# 2022_AESK_UAV_CAN.net
KiCad netlist of a schematic drawn in Altium Designer
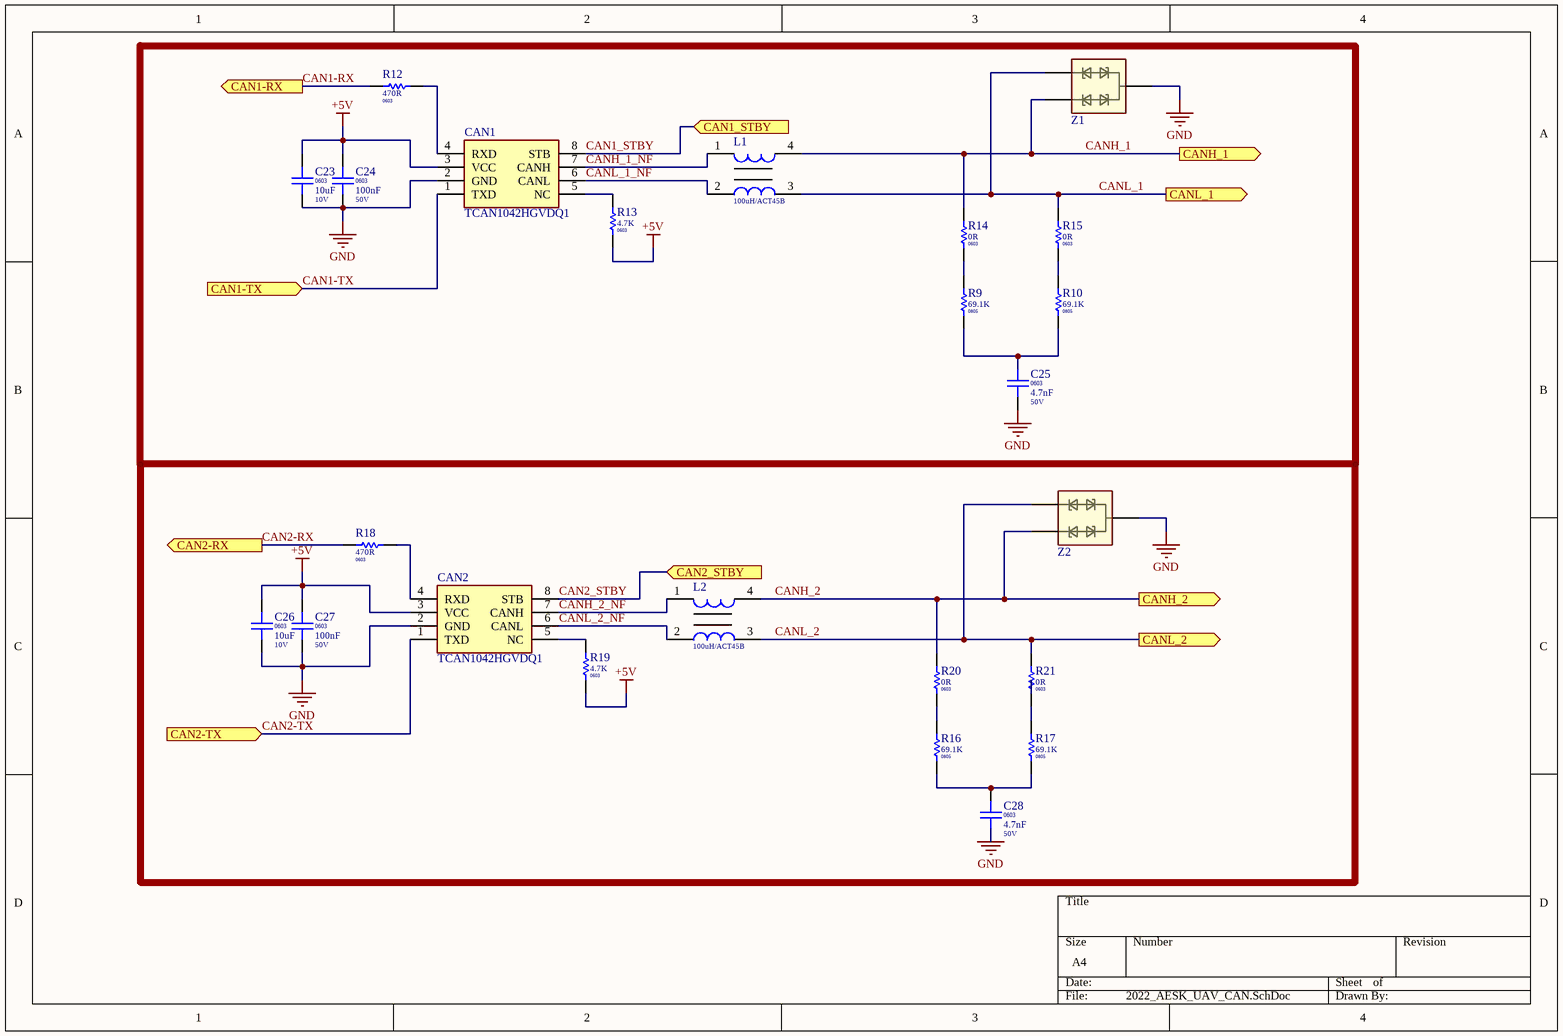
[diagram p0: 2022_AESK_UAV_CAN.SchDoc]

(export (version "E")
  (design (tool "Eeschema 10.0.6"))
  (components
    (comp (ref "C23")
      (value "10uF")
      (footprint "CAPC 0603")
      (description "Capacitor Ceramic 10uF 10V 0603")
      (fields
        (field (name "TOLERANCE") "%10")
        (field (name "PACKAGE / CASE") "0603")
        (field (name "VOLTAGE") "10V")
        (field (name "PART NUMBER") "CAPC0473")
      )
      (libsource (lib "Aesk Database Library") (part "NPCapacitor"))
    )
    (comp (ref "C24")
      (value "100nF")
      (footprint "CAPC 0603")
      (description "Capacitor Ceramic 100nF 50V 0603")
      (fields
        (field (name "TOLERANCE") "%10")
        (field (name "PACKAGE / CASE") "0603")
        (field (name "VOLTAGE") "50V")
        (field (name "PART NUMBER") "CAPC0285")
      )
      (libsource (lib "Aesk Database Library") (part "NPCapacitor"))
    )
    (comp (ref "C25")
      (value "4.7nF")
      (footprint "CAPC 0603")
      (description "Capacitor Ceramic 4.7nF 50V 0603")
      (fields
        (field (name "TOLERANCE") "%10")
        (field (name "PACKAGE / CASE") "0603")
        (field (name "VOLTAGE") "50V")
        (field (name "PART NUMBER") "CAPC0273")
      )
      (libsource (lib "Aesk Database Library") (part "NPCapacitor"))
    )
    (comp (ref "C26")
      (value "10uF")
      (footprint "CAPC 0603")
      (description "Capacitor Ceramic 10uF 10V 0603")
      (fields
        (field (name "TOLERANCE") "%10")
        (field (name "PACKAGE / CASE") "0603")
        (field (name "VOLTAGE") "10V")
        (field (name "PART NUMBER") "CAPC0473")
      )
      (libsource (lib "Aesk Database Library") (part "NPCapacitor"))
    )
    (comp (ref "C27")
      (value "100nF")
      (footprint "CAPC 0603")
      (description "Capacitor Ceramic 100nF 50V 0603")
      (fields
        (field (name "TOLERANCE") "%10")
        (field (name "PACKAGE / CASE") "0603")
        (field (name "VOLTAGE") "50V")
        (field (name "PART NUMBER") "CAPC0285")
      )
      (libsource (lib "Aesk Database Library") (part "NPCapacitor"))
    )
    (comp (ref "C28")
      (value "4.7nF")
      (footprint "CAPC 0603")
      (description "Capacitor Ceramic 4.7nF 50V 0603")
      (fields
        (field (name "TOLERANCE") "%10")
        (field (name "PACKAGE / CASE") "0603")
        (field (name "VOLTAGE") "50V")
        (field (name "PART NUMBER") "CAPC0273")
      )
      (libsource (lib "Aesk Database Library") (part "NPCapacitor"))
    )
    (comp (ref "CAN1")
      (value "TCAN1042HGVDQ1")
      (footprint "SOIC127P600X175-8N")
      (description "Integrated Circuit")
      (fields
        (field (name "MANUFACTURER_PART_NUMBER") "TCAN1042HDRQ1")
        (field (name "MOUSER PART NUMBER") "595-TCAN1042HGVDQ1")
      )
      (libsource (lib "Mainboard_2020_Library") (part "TCAN1042HGVDQ1"))
    )
    (comp (ref "CAN2")
      (value "TCAN1042HGVDQ1")
      (footprint "SOIC127P600X175-8N")
      (description "Integrated Circuit")
      (fields
        (field (name "MANUFACTURER_PART_NUMBER") "TCAN1042HDRQ1")
        (field (name "MOUSER PART NUMBER") "595-TCAN1042HGVDQ1")
      )
      (libsource (lib "Mainboard_2020_Library") (part "TCAN1042HGVDQ1"))
    )
    (comp (ref "L1")
      (value "ACT45B-101-2P-TL003")
      (footprint "TDK_ACT45B_2")
      (description "Inductor")
      (fields (field (name "NAME") "100uH/ACT45B"))
      (libsource (lib "Mainboard_2020_Library") (part "ACT45B-101-2P-TL003"))
    )
    (comp (ref "L2")
      (value "ACT45B-101-2P-TL003")
      (footprint "TDK_ACT45B_2")
      (description "Inductor")
      (fields (field (name "NAME") "100uH/ACT45B"))
      (libsource (lib "Mainboard_2020_Library") (part "ACT45B-101-2P-TL003"))
    )
    (comp (ref "R9")
      (value "69.1K")
      (footprint "RESC 0805")
      (description "68K 0805")
      (fields
        (field (name "TOLERANCE") "%5")
        (field (name "POWER") "1/10W")
        (field (name "PACKAGE / CASE") "0805")
      )
      (libsource (lib "AESK Database Library") (part "Resistor"))
    )
    (comp (ref "R10")
      (value "69.1K")
      (footprint "RESC 0805")
      (description "69.1K 0805")
      (fields
        (field (name "TOLERANCE") "%5")
        (field (name "POWER") "1/10W")
        (field (name "PACKAGE / CASE") "0805")
      )
      (libsource (lib "AESK Database Library") (part "Resistor"))
    )
    (comp (ref "R12")
      (value "470R")
      (footprint "RESC 0603")
      (description "470R 0603")
      (fields
        (field (name "TOLERANCE") "%5")
        (field (name "POWER") "1/10W")
        (field (name "PACKAGE / CASE") "0603")
      )
      (libsource (lib "AESK Database Library") (part "Resistor"))
    )
    (comp (ref "R13")
      (value "4.7K")
      (footprint "RESC 0603")
      (description "4.7K 0603")
      (fields
        (field (name "TOLERANCE") "%5")
        (field (name "POWER") "1/10W")
        (field (name "PACKAGE / CASE") "0603")
      )
      (libsource (lib "AESK Database Library") (part "Resistor"))
    )
    (comp (ref "R14")
      (value "0R")
      (footprint "RESC 0603")
      (description "0R 0603")
      (fields
        (field (name "TOLERANCE") "%5")
        (field (name "POWER") "1/10W")
        (field (name "PACKAGE / CASE") "0603")
      )
      (libsource (lib "Aesk Database Library") (part "Resistor"))
    )
    (comp (ref "R15")
      (value "0R")
      (footprint "RESC 0603")
      (description "0R 0603")
      (fields
        (field (name "TOLERANCE") "%5")
        (field (name "POWER") "1/10W")
        (field (name "PACKAGE / CASE") "0603")
      )
      (libsource (lib "Aesk Database Library") (part "Resistor"))
    )
    (comp (ref "R16")
      (value "69.1K")
      (footprint "RESC 0805")
      (description "68K 0805")
      (fields
        (field (name "TOLERANCE") "%5")
        (field (name "POWER") "1/10W")
        (field (name "PACKAGE / CASE") "0805")
      )
      (libsource (lib "AESK Database Library") (part "Resistor"))
    )
    (comp (ref "R17")
      (value "69.1K")
      (footprint "RESC 0805")
      (description "68K 0805")
      (fields
        (field (name "TOLERANCE") "%5")
        (field (name "POWER") "1/10W")
        (field (name "PACKAGE / CASE") "0805")
      )
      (libsource (lib "AESK Database Library") (part "Resistor"))
    )
    (comp (ref "R18")
      (value "470R")
      (footprint "RESC 0603")
      (description "470R 0603")
      (fields
        (field (name "TOLERANCE") "%5")
        (field (name "POWER") "1/10W")
        (field (name "PACKAGE / CASE") "0603")
      )
      (libsource (lib "AESK Database Library") (part "Resistor"))
    )
    (comp (ref "R19")
      (value "4.7K")
      (footprint "RESC 0603")
      (description "4.7K 0603")
      (fields
        (field (name "TOLERANCE") "%5")
        (field (name "POWER") "1/10W")
        (field (name "PACKAGE / CASE") "0603")
      )
      (libsource (lib "AESK Database Library") (part "Resistor"))
    )
    (comp (ref "R20")
      (value "0R")
      (footprint "RESC 0603")
      (description "0R 0603")
      (fields
        (field (name "TOLERANCE") "%5")
        (field (name "POWER") "1/10W")
        (field (name "PACKAGE / CASE") "0603")
      )
      (libsource (lib "Aesk Database Library") (part "Resistor"))
    )
    (comp (ref "R21")
      (value "0R")
      (footprint "RESC 0603")
      (description "0R 0603")
      (fields
        (field (name "TOLERANCE") "%5")
        (field (name "POWER") "1/10W")
        (field (name "PACKAGE / CASE") "0603")
      )
      (libsource (lib "Aesk Database Library") (part "Resistor"))
    )
    (comp (ref "Z1")
      (value "PESD2CAN,215")
      (footprint "SOT95P230X110-3N")
      (description "Zener Diode")
      (fields
        (field (name "MOUSER PART NUMBER") "771-PESD2CAN-T/R")
        (field (name "RS PART NUMBER") "0508462")
      )
      (libsource (lib "Mainboard_2020_Library") (part "PESD2CAN,215"))
    )
    (comp (ref "Z2")
      (value "PESD2CAN,215")
      (footprint "SOT95P230X110-3N")
      (description "Zener Diode")
      (fields
        (field (name "MOUSER PART NUMBER") "771-PESD2CAN-T/R")
        (field (name "RS PART NUMBER") "0508462")
      )
      (libsource (lib "Mainboard_2020_Library") (part "PESD2CAN,215"))
    )
  )
  (nets
    (net (code "1") (name "+5V") (class "Default")
      (node (ref "C23") (pin "2") (pinfunction "2_2") (pintype "passive"))
      (node (ref "C24") (pin "2") (pinfunction "2_2") (pintype "passive"))
      (node (ref "C26") (pin "2") (pinfunction "2_2") (pintype "passive"))
      (node (ref "C27") (pin "2") (pinfunction "2_2") (pintype "passive"))
      (node (ref "CAN1") (pin "3") (pinfunction "VCC_3") (pintype "power_in"))
      (node (ref "CAN2") (pin "3") (pinfunction "VCC_3") (pintype "power_in"))
      (node (ref "R13") (pin "1") (pinfunction "1_1") (pintype "passive"))
      (node (ref "R19") (pin "1") (pinfunction "1_1") (pintype "passive"))
    )
    (net (code "2") (name "/CAN1-RX") (class "Default")
      (node (ref "R12") (pin "1") (pinfunction "1_1") (pintype "passive"))
    )
    (net (code "3") (name "/CAN1-TX") (class "Default")
      (node (ref "CAN1") (pin "1") (pinfunction "TXD_1") (pintype "passive"))
    )
    (net (code "4") (name "/CAN1_STBY") (class "Default")
      (node (ref "CAN1") (pin "8") (pinfunction "STB_8") (pintype "passive"))
    )
    (net (code "5") (name "/CAN2-RX") (class "Default")
      (node (ref "R18") (pin "1") (pinfunction "1_1") (pintype "passive"))
    )
    (net (code "6") (name "/CAN2-TX") (class "Default")
      (node (ref "CAN2") (pin "1") (pinfunction "TXD_1") (pintype "passive"))
    )
    (net (code "7") (name "/CAN2_STBY") (class "Default")
      (node (ref "CAN2") (pin "8") (pinfunction "STB_8") (pintype "passive"))
    )
    (net (code "8") (name "/CANH_1") (class "Default")
      (node (ref "L1") (pin "4") (pinfunction "4_4") (pintype "passive"))
      (node (ref "R14") (pin "2") (pinfunction "2_2") (pintype "passive"))
      (node (ref "Z1") (pin "2") (pinfunction "2_2") (pintype "passive"))
    )
    (net (code "9") (name "/CANH_1_NF") (class "Default")
      (node (ref "CAN1") (pin "7") (pinfunction "CANH_7") (pintype "passive"))
      (node (ref "L1") (pin "1") (pinfunction "1_1") (pintype "passive"))
    )
    (net (code "10") (name "/CANH_2") (class "Default")
      (node (ref "L2") (pin "4") (pinfunction "4_4") (pintype "passive"))
      (node (ref "R20") (pin "2") (pinfunction "2_2") (pintype "passive"))
      (node (ref "Z2") (pin "2") (pinfunction "2_2") (pintype "passive"))
    )
    (net (code "11") (name "/CANH_2_NF") (class "Default")
      (node (ref "CAN2") (pin "7") (pinfunction "CANH_7") (pintype "passive"))
      (node (ref "L2") (pin "1") (pinfunction "1_1") (pintype "passive"))
    )
    (net (code "12") (name "/CANL_1") (class "Default")
      (node (ref "L1") (pin "3") (pinfunction "3_3") (pintype "passive"))
      (node (ref "R15") (pin "2") (pinfunction "2_2") (pintype "passive"))
      (node (ref "Z1") (pin "1") (pinfunction "1_1") (pintype "passive"))
    )
    (net (code "13") (name "/CANL_1_NF") (class "Default")
      (node (ref "CAN1") (pin "6") (pinfunction "CANL_6") (pintype "passive"))
      (node (ref "L1") (pin "2") (pinfunction "2_2") (pintype "passive"))
    )
    (net (code "14") (name "/CANL_2") (class "Default")
      (node (ref "L2") (pin "3") (pinfunction "3_3") (pintype "passive"))
      (node (ref "R21") (pin "2") (pinfunction "2_2") (pintype "passive"))
      (node (ref "Z2") (pin "1") (pinfunction "1_1") (pintype "passive"))
    )
    (net (code "15") (name "/CANL_2_NF") (class "Default")
      (node (ref "CAN2") (pin "6") (pinfunction "CANL_6") (pintype "passive"))
      (node (ref "L2") (pin "2") (pinfunction "2_2") (pintype "passive"))
    )
    (net (code "16") (name "GND") (class "Default")
      (node (ref "C23") (pin "1") (pinfunction "1_1") (pintype "passive"))
      (node (ref "C24") (pin "1") (pinfunction "1_1") (pintype "passive"))
      (node (ref "C25") (pin "1") (pinfunction "1_1") (pintype "passive"))
      (node (ref "C26") (pin "1") (pinfunction "1_1") (pintype "passive"))
      (node (ref "C27") (pin "1") (pinfunction "1_1") (pintype "passive"))
      (node (ref "C28") (pin "2") (pinfunction "2_2") (pintype "passive"))
      (node (ref "CAN1") (pin "2") (pinfunction "GND_2") (pintype "power_in"))
      (node (ref "CAN2") (pin "2") (pinfunction "GND_2") (pintype "power_in"))
      (node (ref "Z1") (pin "3") (pinfunction "3_3") (pintype "passive"))
      (node (ref "Z2") (pin "3") (pinfunction "3_3") (pintype "passive"))
    )
    (net (code "17") (name "Net-(C25-Pad2)") (class "Default")
      (node (ref "C25") (pin "2") (pinfunction "2_2") (pintype "passive"))
      (node (ref "R10") (pin "1") (pinfunction "1_1") (pintype "passive"))
      (node (ref "R9") (pin "1") (pinfunction "1_1") (pintype "passive"))
    )
    (net (code "18") (name "Net-(C28-Pad1)") (class "Default")
      (node (ref "C28") (pin "1") (pinfunction "1_1") (pintype "passive"))
      (node (ref "R16") (pin "1") (pinfunction "1_1") (pintype "passive"))
      (node (ref "R17") (pin "1") (pinfunction "1_1") (pintype "passive"))
    )
    (net (code "19") (name "Net-(CAN1-NC)") (class "Default")
      (node (ref "CAN1") (pin "5") (pinfunction "NC_5") (pintype "power_in"))
      (node (ref "R13") (pin "2") (pinfunction "2_2") (pintype "passive"))
    )
    (net (code "20") (name "Net-(CAN1-RXD)") (class "Default")
      (node (ref "CAN1") (pin "4") (pinfunction "RXD_4") (pintype "passive"))
      (node (ref "R12") (pin "2") (pinfunction "2_2") (pintype "passive"))
    )
    (net (code "21") (name "Net-(CAN2-NC)") (class "Default")
      (node (ref "CAN2") (pin "5") (pinfunction "NC_5") (pintype "power_in"))
      (node (ref "R19") (pin "2") (pinfunction "2_2") (pintype "passive"))
    )
    (net (code "22") (name "Net-(CAN2-RXD)") (class "Default")
      (node (ref "CAN2") (pin "4") (pinfunction "RXD_4") (pintype "passive"))
      (node (ref "R18") (pin "2") (pinfunction "2_2") (pintype "passive"))
    )
    (net (code "23") (name "Net-(R10-Pad2)") (class "Default")
      (node (ref "R10") (pin "2") (pinfunction "2_2") (pintype "passive"))
      (node (ref "R15") (pin "1") (pinfunction "1_1") (pintype "passive"))
    )
    (net (code "24") (name "Net-(R14-Pad1)") (class "Default")
      (node (ref "R14") (pin "1") (pinfunction "1_1") (pintype "passive"))
      (node (ref "R9") (pin "2") (pinfunction "2_2") (pintype "passive"))
    )
    (net (code "25") (name "Net-(R16-Pad2)") (class "Default")
      (node (ref "R16") (pin "2") (pinfunction "2_2") (pintype "passive"))
      (node (ref "R20") (pin "1") (pinfunction "1_1") (pintype "passive"))
    )
    (net (code "26") (name "Net-(R17-Pad2)") (class "Default")
      (node (ref "R17") (pin "2") (pinfunction "2_2") (pintype "passive"))
      (node (ref "R21") (pin "1") (pinfunction "1_1") (pintype "passive"))
    )
  )
)
